# main.net
KiCad netlist of a schematic drawn in EAGLE
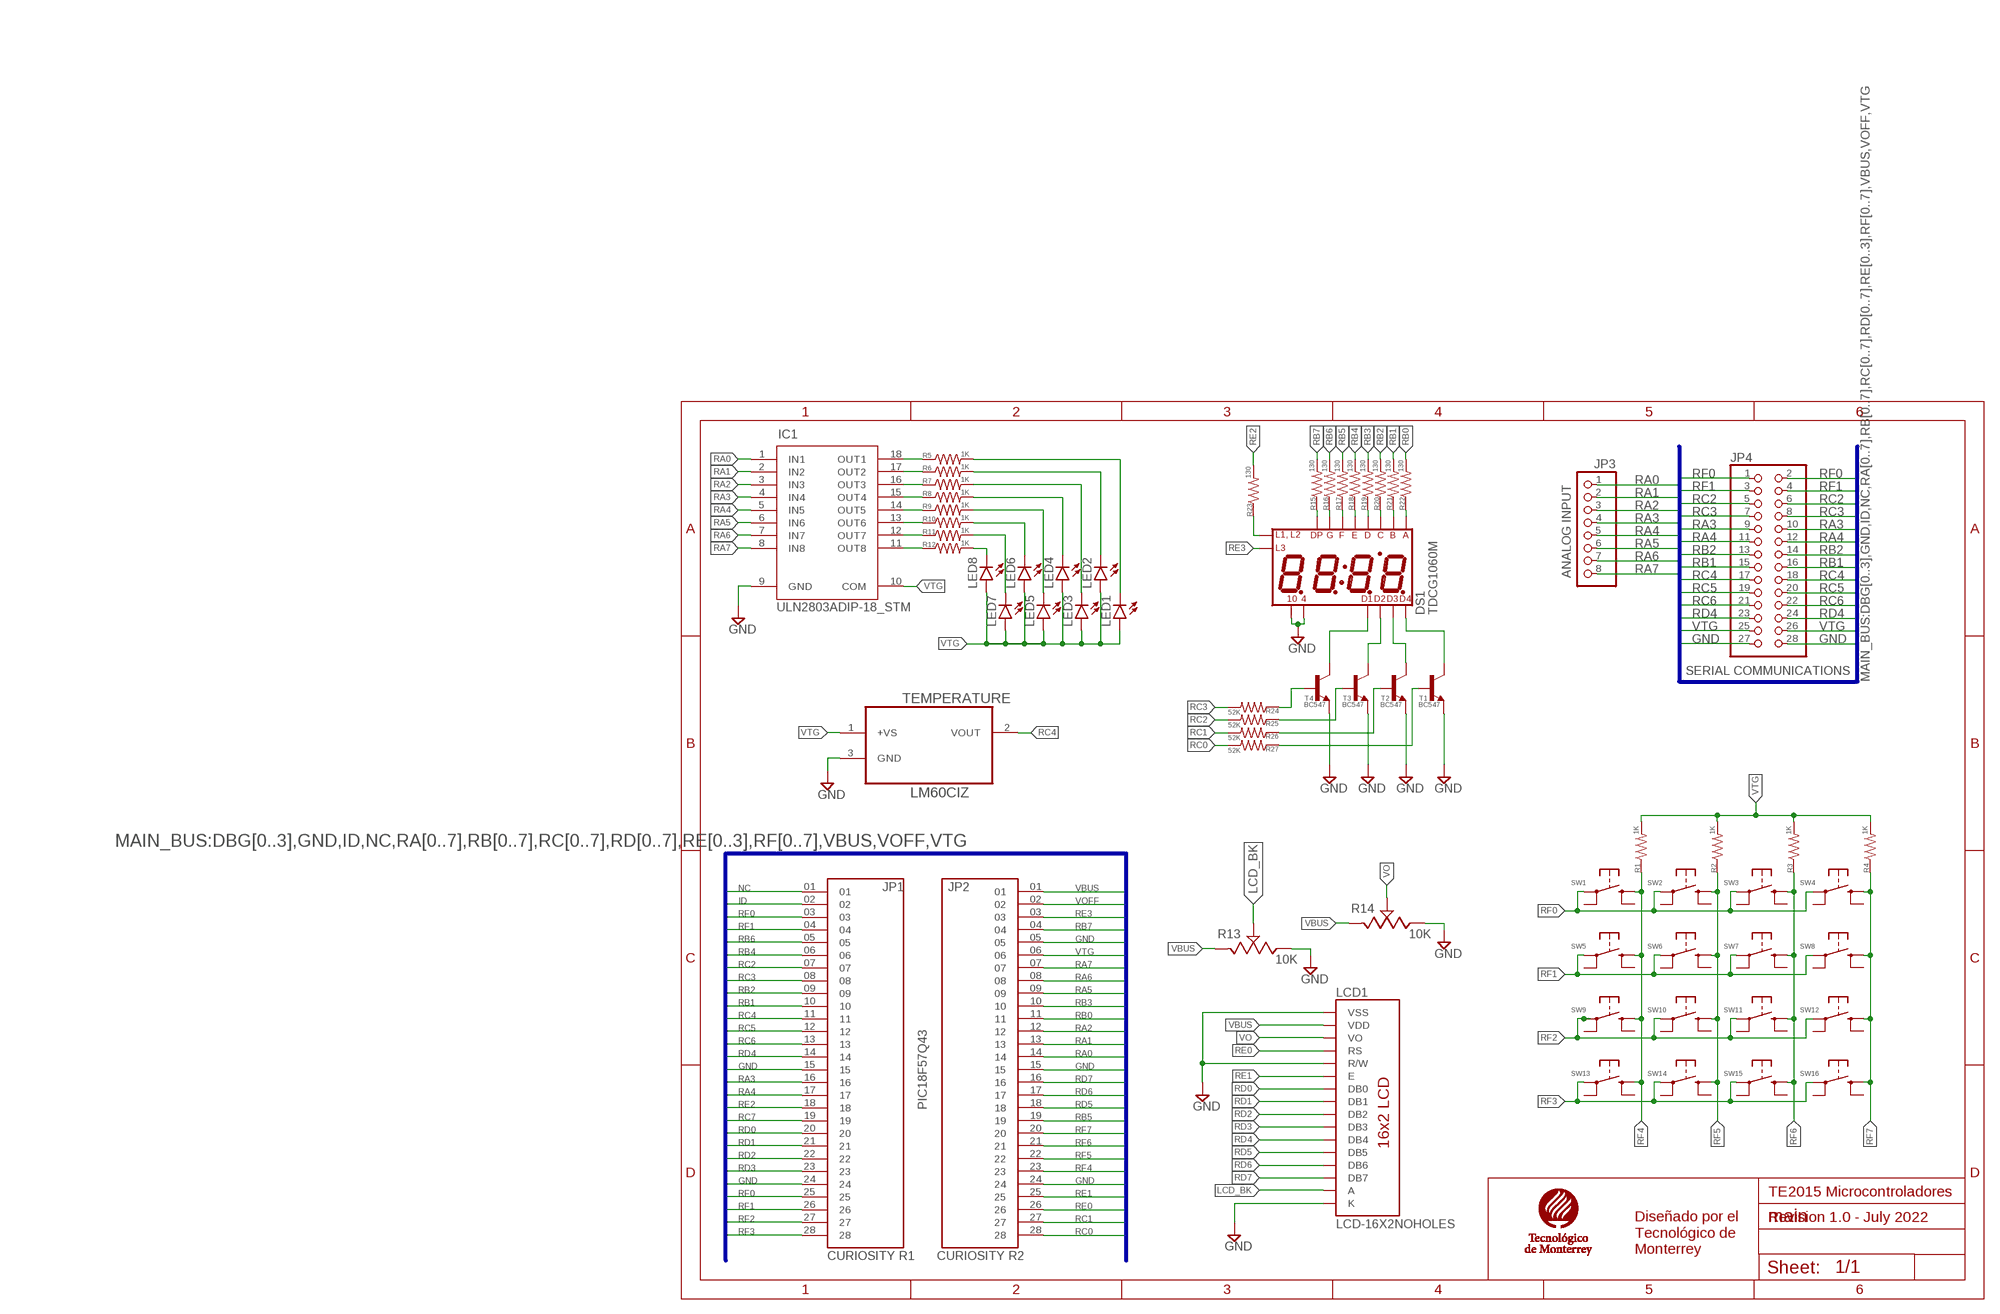
[diagram p0: schematic, sheet 1]

(export (version "E")
  (design (tool "Eeschema 10.0.6"))
  (components
    (comp (ref "DS1")
      (value "TDCG1060M")
      (footprint "eagle-import:DISPLAY_TDCG1060M")
      (fields (field (name "DIGI-KEY_PART_NUMBER") "TDCG1060M-ND") (field (name "MF") "Vishay"))
      (libsource (lib "eagle-import") (part "TDCG1060M"))
    )
    (comp (ref "IC1")
      (value "ULN2803ADIP-18_STM")
      (footprint "eagle-import:DIP-18_STM")
      (fields
        (field (name "MANUFACTURER_PART_NUMBER") "ULN2803A")
        (field (name "COPYRIGHT") "Copyright (C) 2022 Ultra Librarian. All rights reserved.")
      )
      (libsource (lib "eagle-import") (part "ULN2803ADIP-18_STM"))
    )
    (comp (ref "JP1")
      (value "CURIOSITY R1")
      (footprint "eagle-import:SAMTEC_SS-128-T-2")
      (fields
        (field (name "DIGI-KEY_PART_NUMBER") "SAM1117-28-ND")
        (field (name "MF") "Samtec")
        (field (name "MP") "SS-128-T-2")
      )
      (libsource (lib "eagle-import") (part "SS-128-T-2"))
    )
    (comp (ref "JP2")
      (value "CURIOSITY R2")
      (footprint "eagle-import:SAMTEC_SS-128-T-2")
      (fields
        (field (name "DIGI-KEY_PART_NUMBER") "SAM1117-28-ND")
        (field (name "MF") "Samtec")
        (field (name "MP") "SS-128-T-2")
      )
      (libsource (lib "eagle-import") (part "SS-128-T-2"))
    )
    (comp (ref "JP3")
      (value "ANALOG INPUT")
      (footprint "eagle-import:1X08-BIG")
      (libsource (lib "eagle-import") (part "PINHD-1X8BIG"))
    )
    (comp (ref "JP4")
      (value "SERIAL COMMUNICATIONS")
      (footprint "eagle-import:2X14-BIG")
      (libsource (lib "eagle-import") (part "PINHD-2X14-CB"))
    )
    (comp (ref "LCD1")
      (value "LCD-16X2NOHOLES")
      (footprint "eagle-import:LCD-16X2_NOHOLESNOSILK")
      (libsource (lib "eagle-import") (part "LCD-16X2NOHOLES"))
    )
    (comp (ref "LED1")
      (value "LED3MM")
      (footprint "eagle-import:LED3MM")
      (libsource (lib "eagle-import") (part "LED3MM"))
    )
    (comp (ref "LED2")
      (value "LED3MM")
      (footprint "eagle-import:LED3MM")
      (libsource (lib "eagle-import") (part "LED3MM"))
    )
    (comp (ref "LED3")
      (value "LED3MM")
      (footprint "eagle-import:LED3MM")
      (libsource (lib "eagle-import") (part "LED3MM"))
    )
    (comp (ref "LED4")
      (value "LED3MM")
      (footprint "eagle-import:LED3MM")
      (libsource (lib "eagle-import") (part "LED3MM"))
    )
    (comp (ref "LED5")
      (value "LED3MM")
      (footprint "eagle-import:LED3MM")
      (libsource (lib "eagle-import") (part "LED3MM"))
    )
    (comp (ref "LED6")
      (value "LED3MM")
      (footprint "eagle-import:LED3MM")
      (libsource (lib "eagle-import") (part "LED3MM"))
    )
    (comp (ref "LED7")
      (value "LED3MM")
      (footprint "eagle-import:LED3MM")
      (libsource (lib "eagle-import") (part "LED3MM"))
    )
    (comp (ref "LED8")
      (value "LED3MM")
      (footprint "eagle-import:LED3MM")
      (libsource (lib "eagle-import") (part "LED3MM"))
    )
    (comp (ref "R1")
      (value "1K")
      (footprint "eagle-import:0207_10")
      (libsource (lib "eagle-import") (part "R-US"))
    )
    (comp (ref "R2")
      (value "1K")
      (footprint "eagle-import:0207_10")
      (libsource (lib "eagle-import") (part "R-US"))
    )
    (comp (ref "R3")
      (value "1K")
      (footprint "eagle-import:0207_10")
      (libsource (lib "eagle-import") (part "R-US"))
    )
    (comp (ref "R4")
      (value "1K")
      (footprint "eagle-import:0207_10")
      (libsource (lib "eagle-import") (part "R-US"))
    )
    (comp (ref "R5")
      (value "1K")
      (footprint "eagle-import:0207_10")
      (libsource (lib "eagle-import") (part "R-US"))
    )
    (comp (ref "R6")
      (value "1K")
      (footprint "eagle-import:0207_10")
      (libsource (lib "eagle-import") (part "R-US"))
    )
    (comp (ref "R7")
      (value "1K")
      (footprint "eagle-import:0207_10")
      (libsource (lib "eagle-import") (part "R-US"))
    )
    (comp (ref "R8")
      (value "1K")
      (footprint "eagle-import:0207_10")
      (libsource (lib "eagle-import") (part "R-US"))
    )
    (comp (ref "R9")
      (value "1K")
      (footprint "eagle-import:0207_10")
      (libsource (lib "eagle-import") (part "R-US"))
    )
    (comp (ref "R10")
      (value "1K")
      (footprint "eagle-import:0207_10")
      (libsource (lib "eagle-import") (part "R-US"))
    )
    (comp (ref "R11")
      (value "1K")
      (footprint "eagle-import:0207_10")
      (libsource (lib "eagle-import") (part "R-US"))
    )
    (comp (ref "R12")
      (value "1K")
      (footprint "eagle-import:0207_10")
      (libsource (lib "eagle-import") (part "R-US"))
    )
    (comp (ref "R13")
      (value "10K")
      (footprint "eagle-import:3362P-1-103LF")
      (fields
        (field (name "MANUFACTURER") "Bourns Inc.")
        (field (name "MPN") "3362P-1-103LF")
        (field (name "CREATED_PN") "PCBLayout.com")
      )
      (libsource (lib "eagle-import") (part "3362P-1-103LF"))
    )
    (comp (ref "R14")
      (value "10K")
      (footprint "eagle-import:3362P-1-103LF")
      (fields
        (field (name "MANUFACTURER") "Bourns Inc.")
        (field (name "MPN") "3362P-1-103LF")
        (field (name "CREATED_PN") "PCBLayout.com")
      )
      (libsource (lib "eagle-import") (part "3362P-1-103LF"))
    )
    (comp (ref "R15")
      (value "130")
      (footprint "eagle-import:0207_10")
      (libsource (lib "eagle-import") (part "R-US"))
    )
    (comp (ref "R16")
      (value "130")
      (footprint "eagle-import:0207_10")
      (libsource (lib "eagle-import") (part "R-US"))
    )
    (comp (ref "R17")
      (value "130")
      (footprint "eagle-import:0207_10")
      (libsource (lib "eagle-import") (part "R-US"))
    )
    (comp (ref "R18")
      (value "130")
      (footprint "eagle-import:0207_10")
      (libsource (lib "eagle-import") (part "R-US"))
    )
    (comp (ref "R19")
      (value "130")
      (footprint "eagle-import:0207_10")
      (libsource (lib "eagle-import") (part "R-US"))
    )
    (comp (ref "R20")
      (value "130")
      (footprint "eagle-import:0207_10")
      (libsource (lib "eagle-import") (part "R-US"))
    )
    (comp (ref "R21")
      (value "130")
      (footprint "eagle-import:0207_10")
      (libsource (lib "eagle-import") (part "R-US"))
    )
    (comp (ref "R22")
      (value "130")
      (footprint "eagle-import:0207_10")
      (libsource (lib "eagle-import") (part "R-US"))
    )
    (comp (ref "R23")
      (value "130")
      (footprint "eagle-import:0207_10")
      (libsource (lib "eagle-import") (part "R-US"))
    )
    (comp (ref "R24")
      (value "52K")
      (footprint "eagle-import:0207_10")
      (libsource (lib "eagle-import") (part "R-US"))
    )
    (comp (ref "R25")
      (value "52K")
      (footprint "eagle-import:0207_10")
      (libsource (lib "eagle-import") (part "R-US"))
    )
    (comp (ref "R26")
      (value "52K")
      (footprint "eagle-import:0207_10")
      (libsource (lib "eagle-import") (part "R-US"))
    )
    (comp (ref "R27")
      (value "52K")
      (footprint "eagle-import:0207_10")
      (libsource (lib "eagle-import") (part "R-US"))
    )
    (comp (ref "SW1")
      (value "1825910-2")
      (footprint "eagle-import:TE_1825910-2")
      (fields (field (name "MF") "TE Connectivity"))
      (libsource (lib "eagle-import") (part "1825910-2"))
    )
    (comp (ref "SW2")
      (value "1825910-2")
      (footprint "eagle-import:TE_1825910-2")
      (fields (field (name "MF") "TE Connectivity"))
      (libsource (lib "eagle-import") (part "1825910-2"))
    )
    (comp (ref "SW3")
      (value "1825910-2")
      (footprint "eagle-import:TE_1825910-2")
      (fields (field (name "MF") "TE Connectivity"))
      (libsource (lib "eagle-import") (part "1825910-2"))
    )
    (comp (ref "SW4")
      (value "1825910-2")
      (footprint "eagle-import:TE_1825910-2")
      (fields (field (name "MF") "TE Connectivity"))
      (libsource (lib "eagle-import") (part "1825910-2"))
    )
    (comp (ref "SW5")
      (value "1825910-2")
      (footprint "eagle-import:TE_1825910-2")
      (fields (field (name "MF") "TE Connectivity"))
      (libsource (lib "eagle-import") (part "1825910-2"))
    )
    (comp (ref "SW6")
      (value "1825910-2")
      (footprint "eagle-import:TE_1825910-2")
      (fields (field (name "MF") "TE Connectivity"))
      (libsource (lib "eagle-import") (part "1825910-2"))
    )
    (comp (ref "SW7")
      (value "1825910-2")
      (footprint "eagle-import:TE_1825910-2")
      (fields (field (name "MF") "TE Connectivity"))
      (libsource (lib "eagle-import") (part "1825910-2"))
    )
    (comp (ref "SW8")
      (value "1825910-2")
      (footprint "eagle-import:TE_1825910-2")
      (fields (field (name "MF") "TE Connectivity"))
      (libsource (lib "eagle-import") (part "1825910-2"))
    )
    (comp (ref "SW9")
      (value "1825910-2")
      (footprint "eagle-import:TE_1825910-2")
      (fields (field (name "MF") "TE Connectivity"))
      (libsource (lib "eagle-import") (part "1825910-2"))
    )
    (comp (ref "SW10")
      (value "1825910-2")
      (footprint "eagle-import:TE_1825910-2")
      (fields (field (name "MF") "TE Connectivity"))
      (libsource (lib "eagle-import") (part "1825910-2"))
    )
    (comp (ref "SW11")
      (value "1825910-2")
      (footprint "eagle-import:TE_1825910-2")
      (fields (field (name "MF") "TE Connectivity"))
      (libsource (lib "eagle-import") (part "1825910-2"))
    )
    (comp (ref "SW12")
      (value "1825910-2")
      (footprint "eagle-import:TE_1825910-2")
      (fields (field (name "MF") "TE Connectivity"))
      (libsource (lib "eagle-import") (part "1825910-2"))
    )
    (comp (ref "SW13")
      (value "1825910-2")
      (footprint "eagle-import:TE_1825910-2")
      (fields (field (name "MF") "TE Connectivity"))
      (libsource (lib "eagle-import") (part "1825910-2"))
    )
    (comp (ref "SW14")
      (value "1825910-2")
      (footprint "eagle-import:TE_1825910-2")
      (fields (field (name "MF") "TE Connectivity"))
      (libsource (lib "eagle-import") (part "1825910-2"))
    )
    (comp (ref "SW15")
      (value "1825910-2")
      (footprint "eagle-import:TE_1825910-2")
      (fields (field (name "MF") "TE Connectivity"))
      (libsource (lib "eagle-import") (part "1825910-2"))
    )
    (comp (ref "SW16")
      (value "1825910-2")
      (footprint "eagle-import:TE_1825910-2")
      (fields (field (name "MF") "TE Connectivity"))
      (libsource (lib "eagle-import") (part "1825910-2"))
    )
    (comp (ref "T1")
      (value "BC547")
      (footprint "eagle-import:TO92")
      (libsource (lib "eagle-import") (part "BC547"))
    )
    (comp (ref "T2")
      (value "BC547")
      (footprint "eagle-import:TO92")
      (libsource (lib "eagle-import") (part "BC547"))
    )
    (comp (ref "T3")
      (value "BC547")
      (footprint "eagle-import:TO92")
      (libsource (lib "eagle-import") (part "BC547"))
    )
    (comp (ref "T4")
      (value "BC547")
      (footprint "eagle-import:TO92")
      (libsource (lib "eagle-import") (part "BC547"))
    )
    (comp (ref "TEC1")
      (value "TEC_LOGO")
      (footprint "eagle-import:TEC_LOGO")
      (libsource (lib "eagle-import") (part "TEC_LOGO"))
    )
    (comp (ref "TEMPERATURE")
      (value "LM60CIZ")
      (footprint "eagle-import:TO92_")
      (libsource (lib "eagle-import") (part "LM60CIZ"))
    )
  )
  (nets
    (net (code "1") (name "/ID") (class "Default")
      (node (ref "JP1") (pin "02") (pinfunction "02_02") (pintype "passive"))
    )
    (net (code "2") (name "/NC") (class "Default")
      (node (ref "JP1") (pin "01") (pinfunction "01_01") (pintype "passive"))
    )
    (net (code "3") (name "/RC5") (class "Default")
      (node (ref "JP1") (pin "12") (pinfunction "12_12") (pintype "passive"))
      (node (ref "JP4") (pin "19") (pinfunction "19_19") (pintype "passive"))
      (node (ref "JP4") (pin "20") (pinfunction "20_20") (pintype "passive"))
    )
    (net (code "4") (name "/RC6") (class "Default")
      (node (ref "JP1") (pin "13") (pinfunction "13_13") (pintype "passive"))
      (node (ref "JP4") (pin "21") (pinfunction "21_21") (pintype "passive"))
      (node (ref "JP4") (pin "22") (pinfunction "22_22") (pintype "passive"))
    )
    (net (code "5") (name "/RC7") (class "Default")
      (node (ref "JP1") (pin "19") (pinfunction "19_19") (pintype "passive"))
    )
    (net (code "6") (name "/VOFF") (class "Default")
      (node (ref "JP2") (pin "02") (pinfunction "02_02") (pintype "passive"))
    )
    (net (code "8") (name "GND") (class "Default")
      (node (ref "DS1") (pin "10") (pinfunction "10_10") (pintype "passive"))
      (node (ref "DS1") (pin "4") (pinfunction "4_4") (pintype "passive"))
      (node (ref "IC1") (pin "9") (pinfunction "GND_9") (pintype "power_in"))
      (node (ref "JP1") (pin "15") (pinfunction "15_15") (pintype "passive"))
      (node (ref "JP1") (pin "24") (pinfunction "24_24") (pintype "passive"))
      (node (ref "JP2") (pin "05") (pinfunction "05_05") (pintype "passive"))
      (node (ref "JP2") (pin "15") (pinfunction "15_15") (pintype "passive"))
      (node (ref "JP2") (pin "24") (pinfunction "24_24") (pintype "passive"))
      (node (ref "JP4") (pin "27") (pinfunction "27_27") (pintype "passive"))
      (node (ref "JP4") (pin "28") (pinfunction "28_28") (pintype "passive"))
      (node (ref "LCD1") (pin "1") (pinfunction "VSS_1") (pintype "power_in"))
      (node (ref "LCD1") (pin "16") (pinfunction "K_16") (pintype "power_in"))
      (node (ref "LCD1") (pin "5") (pinfunction "R/W_5") (pintype "input"))
      (node (ref "R13") (pin "3") (pinfunction "3_3") (pintype "passive"))
      (node (ref "R14") (pin "3") (pinfunction "3_3") (pintype "passive"))
      (node (ref "T1") (pin "1") (pinfunction "E_1") (pintype "passive"))
      (node (ref "T2") (pin "1") (pinfunction "E_1") (pintype "passive"))
      (node (ref "T3") (pin "1") (pinfunction "E_1") (pintype "passive"))
      (node (ref "T4") (pin "1") (pinfunction "E_1") (pintype "passive"))
      (node (ref "TEMPERATURE") (pin "3") (pinfunction "GND_3") (pintype "passive"))
    )
    (net (code "9") (name "LCD_BK") (class "Default")
      (node (ref "LCD1") (pin "15") (pinfunction "A_15") (pintype "power_in"))
      (node (ref "R13") (pin "2") (pinfunction "2_2") (pintype "passive"))
    )
    (net (code "10") (name "Net-(DS1-A)") (class "Default")
      (node (ref "DS1") (pin "14") (pinfunction "A_14") (pintype "passive"))
      (node (ref "R22") (pin "1") (pinfunction "1_1") (pintype "passive"))
    )
    (net (code "11") (name "Net-(DS1-B)") (class "Default")
      (node (ref "DS1") (pin "16") (pinfunction "B_16") (pintype "passive"))
      (node (ref "R21") (pin "1") (pinfunction "1_1") (pintype "passive"))
    )
    (net (code "12") (name "Net-(DS1-C)") (class "Default")
      (node (ref "DS1") (pin "13") (pinfunction "C_13") (pintype "passive"))
      (node (ref "R20") (pin "1") (pinfunction "1_1") (pintype "passive"))
    )
    (net (code "13") (name "Net-(DS1-D)") (class "Default")
      (node (ref "DS1") (pin "3") (pinfunction "D_3") (pintype "passive"))
      (node (ref "R19") (pin "1") (pinfunction "1_1") (pintype "passive"))
    )
    (net (code "14") (name "Net-(DS1-DIG1)") (class "Default")
      (node (ref "DS1") (pin "1") (pinfunction "DIG1_1") (pintype "passive"))
      (node (ref "T4") (pin "3") (pinfunction "C_3") (pintype "passive"))
    )
    (net (code "15") (name "Net-(DS1-DIG2)") (class "Default")
      (node (ref "DS1") (pin "2") (pinfunction "DIG2_2") (pintype "passive"))
      (node (ref "T3") (pin "3") (pinfunction "C_3") (pintype "passive"))
    )
    (net (code "16") (name "Net-(DS1-DIG3)") (class "Default")
      (node (ref "DS1") (pin "6") (pinfunction "DIG3_6") (pintype "passive"))
      (node (ref "T2") (pin "3") (pinfunction "C_3") (pintype "passive"))
    )
    (net (code "17") (name "Net-(DS1-DIG4)") (class "Default")
      (node (ref "DS1") (pin "8") (pinfunction "DIG4_8") (pintype "passive"))
      (node (ref "T1") (pin "3") (pinfunction "C_3") (pintype "passive"))
    )
    (net (code "18") (name "Net-(DS1-DP)") (class "Default")
      (node (ref "DS1") (pin "7") (pinfunction "DP_7") (pintype "passive"))
      (node (ref "R15") (pin "1") (pinfunction "1_1") (pintype "passive"))
    )
    (net (code "19") (name "Net-(DS1-E)") (class "Default")
      (node (ref "DS1") (pin "5") (pinfunction "E_5") (pintype "passive"))
      (node (ref "R18") (pin "1") (pinfunction "1_1") (pintype "passive"))
    )
    (net (code "20") (name "Net-(DS1-F)") (class "Default")
      (node (ref "DS1") (pin "11") (pinfunction "F_11") (pintype "passive"))
      (node (ref "R17") (pin "1") (pinfunction "1_1") (pintype "passive"))
    )
    (net (code "21") (name "Net-(DS1-G)") (class "Default")
      (node (ref "DS1") (pin "15") (pinfunction "G_15") (pintype "passive"))
      (node (ref "R16") (pin "1") (pinfunction "1_1") (pintype "passive"))
    )
    (net (code "22") (name "Net-(DS1-L1_L2)") (class "Default")
      (node (ref "DS1") (pin "12") (pinfunction "L1_L2_12") (pintype "passive"))
      (node (ref "R23") (pin "1") (pinfunction "1_1") (pintype "passive"))
    )
    (net (code "23") (name "Net-(IC1-OUT1)") (class "Default")
      (node (ref "IC1") (pin "18") (pinfunction "OUT1_18") (pintype "passive"))
      (node (ref "R5") (pin "1") (pinfunction "1_1") (pintype "passive"))
    )
    (net (code "24") (name "Net-(IC1-OUT2)") (class "Default")
      (node (ref "IC1") (pin "17") (pinfunction "OUT2_17") (pintype "passive"))
      (node (ref "R6") (pin "1") (pinfunction "1_1") (pintype "passive"))
    )
    (net (code "25") (name "Net-(IC1-OUT3)") (class "Default")
      (node (ref "IC1") (pin "16") (pinfunction "OUT3_16") (pintype "passive"))
      (node (ref "R7") (pin "1") (pinfunction "1_1") (pintype "passive"))
    )
    (net (code "26") (name "Net-(IC1-OUT4)") (class "Default")
      (node (ref "IC1") (pin "15") (pinfunction "OUT4_15") (pintype "passive"))
      (node (ref "R8") (pin "1") (pinfunction "1_1") (pintype "passive"))
    )
    (net (code "27") (name "Net-(IC1-OUT5)") (class "Default")
      (node (ref "IC1") (pin "14") (pinfunction "OUT5_14") (pintype "passive"))
      (node (ref "R9") (pin "1") (pinfunction "1_1") (pintype "passive"))
    )
    (net (code "28") (name "Net-(IC1-OUT6)") (class "Default")
      (node (ref "IC1") (pin "13") (pinfunction "OUT6_13") (pintype "passive"))
      (node (ref "R10") (pin "1") (pinfunction "1_1") (pintype "passive"))
    )
    (net (code "29") (name "Net-(IC1-OUT7)") (class "Default")
      (node (ref "IC1") (pin "12") (pinfunction "OUT7_12") (pintype "passive"))
      (node (ref "R11") (pin "1") (pinfunction "1_1") (pintype "passive"))
    )
    (net (code "30") (name "Net-(IC1-OUT8)") (class "Default")
      (node (ref "IC1") (pin "11") (pinfunction "OUT8_11") (pintype "passive"))
      (node (ref "R12") (pin "1") (pinfunction "1_1") (pintype "passive"))
    )
    (net (code "31") (name "Net-(LED1-C)") (class "Default")
      (node (ref "LED1") (pin "K") (pinfunction "C_K") (pintype "passive"))
      (node (ref "R5") (pin "2") (pinfunction "2_2") (pintype "passive"))
    )
    (net (code "32") (name "Net-(LED2-C)") (class "Default")
      (node (ref "LED2") (pin "K") (pinfunction "C_K") (pintype "passive"))
      (node (ref "R6") (pin "2") (pinfunction "2_2") (pintype "passive"))
    )
    (net (code "33") (name "Net-(LED3-C)") (class "Default")
      (node (ref "LED3") (pin "K") (pinfunction "C_K") (pintype "passive"))
      (node (ref "R7") (pin "2") (pinfunction "2_2") (pintype "passive"))
    )
    (net (code "34") (name "Net-(LED4-C)") (class "Default")
      (node (ref "LED4") (pin "K") (pinfunction "C_K") (pintype "passive"))
      (node (ref "R8") (pin "2") (pinfunction "2_2") (pintype "passive"))
    )
    (net (code "35") (name "Net-(LED5-C)") (class "Default")
      (node (ref "LED5") (pin "K") (pinfunction "C_K") (pintype "passive"))
      (node (ref "R9") (pin "2") (pinfunction "2_2") (pintype "passive"))
    )
    (net (code "36") (name "Net-(LED6-C)") (class "Default")
      (node (ref "LED6") (pin "K") (pinfunction "C_K") (pintype "passive"))
      (node (ref "R10") (pin "2") (pinfunction "2_2") (pintype "passive"))
    )
    (net (code "37") (name "Net-(LED7-C)") (class "Default")
      (node (ref "LED7") (pin "K") (pinfunction "C_K") (pintype "passive"))
      (node (ref "R11") (pin "2") (pinfunction "2_2") (pintype "passive"))
    )
    (net (code "38") (name "Net-(LED8-C)") (class "Default")
      (node (ref "LED8") (pin "K") (pinfunction "C_K") (pintype "passive"))
      (node (ref "R12") (pin "2") (pinfunction "2_2") (pintype "passive"))
    )
    (net (code "39") (name "Net-(T1-B)") (class "Default")
      (node (ref "R27") (pin "1") (pinfunction "1_1") (pintype "passive"))
      (node (ref "T1") (pin "2") (pinfunction "B_2") (pintype "passive"))
    )
    (net (code "40") (name "Net-(T2-B)") (class "Default")
      (node (ref "R26") (pin "1") (pinfunction "1_1") (pintype "passive"))
      (node (ref "T2") (pin "2") (pinfunction "B_2") (pintype "passive"))
    )
    (net (code "41") (name "Net-(T3-B)") (class "Default")
      (node (ref "R25") (pin "1") (pinfunction "1_1") (pintype "passive"))
      (node (ref "T3") (pin "2") (pinfunction "B_2") (pintype "passive"))
    )
    (net (code "42") (name "Net-(T4-B)") (class "Default")
      (node (ref "R24") (pin "1") (pinfunction "1_1") (pintype "passive"))
      (node (ref "T4") (pin "2") (pinfunction "B_2") (pintype "passive"))
    )
    (net (code "43") (name "RA0") (class "Default")
      (node (ref "IC1") (pin "1") (pinfunction "IN1_1") (pintype "input"))
      (node (ref "JP2") (pin "14") (pinfunction "14_14") (pintype "passive"))
      (node (ref "JP3") (pin "1") (pinfunction "1_1") (pintype "passive"))
    )
    (net (code "44") (name "RA1") (class "Default")
      (node (ref "IC1") (pin "2") (pinfunction "IN2_2") (pintype "input"))
      (node (ref "JP2") (pin "13") (pinfunction "13_13") (pintype "passive"))
      (node (ref "JP3") (pin "2") (pinfunction "2_2") (pintype "passive"))
    )
    (net (code "45") (name "RA2") (class "Default")
      (node (ref "IC1") (pin "3") (pinfunction "IN3_3") (pintype "input"))
      (node (ref "JP2") (pin "12") (pinfunction "12_12") (pintype "passive"))
      (node (ref "JP3") (pin "3") (pinfunction "3_3") (pintype "passive"))
    )
    (net (code "46") (name "RA3") (class "Default")
      (node (ref "IC1") (pin "4") (pinfunction "IN4_4") (pintype "input"))
      (node (ref "JP1") (pin "16") (pinfunction "16_16") (pintype "passive"))
      (node (ref "JP3") (pin "4") (pinfunction "4_4") (pintype "passive"))
      (node (ref "JP4") (pin "10") (pinfunction "10_10") (pintype "passive"))
      (node (ref "JP4") (pin "9") (pinfunction "9_9") (pintype "passive"))
    )
    (net (code "47") (name "RA4") (class "Default")
      (node (ref "IC1") (pin "5") (pinfunction "IN5_5") (pintype "input"))
      (node (ref "JP1") (pin "17") (pinfunction "17_17") (pintype "passive"))
      (node (ref "JP3") (pin "5") (pinfunction "5_5") (pintype "passive"))
      (node (ref "JP4") (pin "11") (pinfunction "11_11") (pintype "passive"))
      (node (ref "JP4") (pin "12") (pinfunction "12_12") (pintype "passive"))
    )
    (net (code "48") (name "RA5") (class "Default")
      (node (ref "IC1") (pin "6") (pinfunction "IN6_6") (pintype "input"))
      (node (ref "JP2") (pin "09") (pinfunction "09_09") (pintype "passive"))
      (node (ref "JP3") (pin "6") (pinfunction "6_6") (pintype "passive"))
    )
    (net (code "49") (name "RA6") (class "Default")
      (node (ref "IC1") (pin "7") (pinfunction "IN7_7") (pintype "input"))
      (node (ref "JP2") (pin "08") (pinfunction "08_08") (pintype "passive"))
      (node (ref "JP3") (pin "7") (pinfunction "7_7") (pintype "passive"))
    )
    (net (code "50") (name "RA7") (class "Default")
      (node (ref "IC1") (pin "8") (pinfunction "IN8_8") (pintype "input"))
      (node (ref "JP2") (pin "07") (pinfunction "07_07") (pintype "passive"))
      (node (ref "JP3") (pin "8") (pinfunction "8_8") (pintype "passive"))
    )
    (net (code "51") (name "RB0") (class "Default")
      (node (ref "JP2") (pin "11") (pinfunction "11_11") (pintype "passive"))
      (node (ref "R22") (pin "2") (pinfunction "2_2") (pintype "passive"))
    )
    (net (code "52") (name "RB1") (class "Default")
      (node (ref "JP1") (pin "10") (pinfunction "10_10") (pintype "passive"))
      (node (ref "JP4") (pin "15") (pinfunction "15_15") (pintype "passive"))
      (node (ref "JP4") (pin "16") (pinfunction "16_16") (pintype "passive"))
      (node (ref "R21") (pin "2") (pinfunction "2_2") (pintype "passive"))
    )
    (net (code "53") (name "RB2") (class "Default")
      (node (ref "JP1") (pin "09") (pinfunction "09_09") (pintype "passive"))
      (node (ref "JP4") (pin "13") (pinfunction "13_13") (pintype "passive"))
      (node (ref "JP4") (pin "14") (pinfunction "14_14") (pintype "passive"))
      (node (ref "R20") (pin "2") (pinfunction "2_2") (pintype "passive"))
    )
    (net (code "54") (name "RB3") (class "Default")
      (node (ref "JP2") (pin "10") (pinfunction "10_10") (pintype "passive"))
      (node (ref "R19") (pin "2") (pinfunction "2_2") (pintype "passive"))
    )
    (net (code "55") (name "RB4") (class "Default")
      (node (ref "JP1") (pin "06") (pinfunction "06_06") (pintype "passive"))
      (node (ref "R18") (pin "2") (pinfunction "2_2") (pintype "passive"))
    )
    (net (code "56") (name "RB5") (class "Default")
      (node (ref "JP2") (pin "19") (pinfunction "19_19") (pintype "passive"))
      (node (ref "R17") (pin "2") (pinfunction "2_2") (pintype "passive"))
    )
    (net (code "57") (name "RB6") (class "Default")
      (node (ref "JP1") (pin "05") (pinfunction "05_05") (pintype "passive"))
      (node (ref "R16") (pin "2") (pinfunction "2_2") (pintype "passive"))
    )
    (net (code "58") (name "RB7") (class "Default")
      (node (ref "JP2") (pin "04") (pinfunction "04_04") (pintype "passive"))
      (node (ref "R15") (pin "2") (pinfunction "2_2") (pintype "passive"))
    )
    (net (code "59") (name "RC0") (class "Default")
      (node (ref "JP2") (pin "28") (pinfunction "28_28") (pintype "passive"))
      (node (ref "R27") (pin "2") (pinfunction "2_2") (pintype "passive"))
    )
    (net (code "60") (name "RC1") (class "Default")
      (node (ref "JP2") (pin "27") (pinfunction "27_27") (pintype "passive"))
      (node (ref "R26") (pin "2") (pinfunction "2_2") (pintype "passive"))
    )
    (net (code "61") (name "RC2") (class "Default")
      (node (ref "JP1") (pin "07") (pinfunction "07_07") (pintype "passive"))
      (node (ref "JP4") (pin "5") (pinfunction "5_5") (pintype "passive"))
      (node (ref "JP4") (pin "6") (pinfunction "6_6") (pintype "passive"))
      (node (ref "R25") (pin "2") (pinfunction "2_2") (pintype "passive"))
    )
    (net (code "62") (name "RC3") (class "Default")
      (node (ref "JP1") (pin "08") (pinfunction "08_08") (pintype "passive"))
      (node (ref "JP4") (pin "7") (pinfunction "7_7") (pintype "passive"))
      (node (ref "JP4") (pin "8") (pinfunction "8_8") (pintype "passive"))
      (node (ref "R24") (pin "2") (pinfunction "2_2") (pintype "passive"))
    )
    (net (code "63") (name "RC4") (class "Default")
      (node (ref "JP1") (pin "11") (pinfunction "11_11") (pintype "passive"))
      (node (ref "JP4") (pin "17") (pinfunction "17_17") (pintype "passive"))
      (node (ref "JP4") (pin "18") (pinfunction "18_18") (pintype "passive"))
      (node (ref "TEMPERATURE") (pin "2") (pinfunction "VOUT_2") (pintype "output"))
    )
    (net (code "64") (name "RD0") (class "Default")
      (node (ref "JP1") (pin "20") (pinfunction "20_20") (pintype "passive"))
      (node (ref "LCD1") (pin "7") (pinfunction "DB0_7") (pintype "bidirectional"))
    )
    (net (code "65") (name "RD1") (class "Default")
      (node (ref "JP1") (pin "21") (pinfunction "21_21") (pintype "passive"))
      (node (ref "LCD1") (pin "8") (pinfunction "DB1_8") (pintype "bidirectional"))
    )
    (net (code "66") (name "RD2") (class "Default")
      (node (ref "JP1") (pin "22") (pinfunction "22_22") (pintype "passive"))
      (node (ref "LCD1") (pin "9") (pinfunction "DB2_9") (pintype "bidirectional"))
    )
    (net (code "67") (name "RD3") (class "Default")
      (node (ref "JP1") (pin "23") (pinfunction "23_23") (pintype "passive"))
      (node (ref "LCD1") (pin "10") (pinfunction "DB3_10") (pintype "bidirectional"))
    )
    (net (code "68") (name "RD4") (class "Default")
      (node (ref "JP1") (pin "14") (pinfunction "14_14") (pintype "passive"))
      (node (ref "JP4") (pin "23") (pinfunction "23_23") (pintype "passive"))
      (node (ref "JP4") (pin "24") (pinfunction "24_24") (pintype "passive"))
      (node (ref "LCD1") (pin "11") (pinfunction "DB4_11") (pintype "bidirectional"))
    )
    (net (code "69") (name "RD5") (class "Default")
      (node (ref "JP2") (pin "18") (pinfunction "18_18") (pintype "passive"))
      (node (ref "LCD1") (pin "12") (pinfunction "DB5_12") (pintype "bidirectional"))
    )
    (net (code "70") (name "RD6") (class "Default")
      (node (ref "JP2") (pin "17") (pinfunction "17_17") (pintype "passive"))
      (node (ref "LCD1") (pin "13") (pinfunction "DB6_13") (pintype "bidirectional"))
    )
    (net (code "71") (name "RD7") (class "Default")
      (node (ref "JP2") (pin "16") (pinfunction "16_16") (pintype "passive"))
      (node (ref "LCD1") (pin "14") (pinfunction "DB7_14") (pintype "bidirectional"))
    )
    (net (code "72") (name "RE0") (class "Default")
      (node (ref "JP2") (pin "26") (pinfunction "26_26") (pintype "passive"))
      (node (ref "LCD1") (pin "4") (pinfunction "RS_4") (pintype "input"))
    )
    (net (code "73") (name "RE1") (class "Default")
      (node (ref "JP2") (pin "25") (pinfunction "25_25") (pintype "passive"))
      (node (ref "LCD1") (pin "6") (pinfunction "E_6") (pintype "input"))
    )
    (net (code "74") (name "RE2") (class "Default")
      (node (ref "JP1") (pin "18") (pinfunction "18_18") (pintype "passive"))
      (node (ref "R23") (pin "2") (pinfunction "2_2") (pintype "passive"))
    )
    (net (code "75") (name "RE3") (class "Default")
      (node (ref "DS1") (pin "9") (pinfunction "L3_9") (pintype "passive"))
      (node (ref "JP2") (pin "03") (pinfunction "03_03") (pintype "passive"))
    )
    (net (code "76") (name "RF0") (class "Default")
      (node (ref "JP1") (pin "03") (pinfunction "03_03") (pintype "passive"))
      (node (ref "JP1") (pin "25") (pinfunction "25_25") (pintype "passive"))
      (node (ref "JP4") (pin "1") (pinfunction "1_1") (pintype "passive"))
      (node (ref "JP4") (pin "2") (pinfunction "2_2") (pintype "passive"))
      (node (ref "SW1") (pin "1") (pinfunction "P_1") (pintype "passive"))
      (node (ref "SW2") (pin "1") (pinfunction "P_1") (pintype "passive"))
      (node (ref "SW3") (pin "1") (pinfunction "P_1") (pintype "passive"))
      (node (ref "SW4") (pin "1") (pinfunction "P_1") (pintype "passive"))
    )
    (net (code "77") (name "RF1") (class "Default")
      (node (ref "JP1") (pin "04") (pinfunction "04_04") (pintype "passive"))
      (node (ref "JP1") (pin "26") (pinfunction "26_26") (pintype "passive"))
      (node (ref "JP4") (pin "3") (pinfunction "3_3") (pintype "passive"))
      (node (ref "JP4") (pin "4") (pinfunction "4_4") (pintype "passive"))
      (node (ref "SW5") (pin "1") (pinfunction "P_1") (pintype "passive"))
      (node (ref "SW6") (pin "1") (pinfunction "P_1") (pintype "passive"))
      (node (ref "SW7") (pin "1") (pinfunction "P_1") (pintype "passive"))
      (node (ref "SW8") (pin "1") (pinfunction "P_1") (pintype "passive"))
    )
    (net (code "78") (name "RF2") (class "Default")
      (node (ref "JP1") (pin "27") (pinfunction "27_27") (pintype "passive"))
      (node (ref "SW10") (pin "1") (pinfunction "P_1") (pintype "passive"))
      (node (ref "SW11") (pin "1") (pinfunction "P_1") (pintype "passive"))
      (node (ref "SW12") (pin "1") (pinfunction "P_1") (pintype "passive"))
      (node (ref "SW9") (pin "1") (pinfunction "P_1") (pintype "passive"))
    )
    (net (code "79") (name "RF3") (class "Default")
      (node (ref "JP1") (pin "28") (pinfunction "28_28") (pintype "passive"))
      (node (ref "SW13") (pin "1") (pinfunction "P_1") (pintype "passive"))
      (node (ref "SW14") (pin "1") (pinfunction "P_1") (pintype "passive"))
      (node (ref "SW15") (pin "1") (pinfunction "P_1") (pintype "passive"))
      (node (ref "SW16") (pin "1") (pinfunction "P_1") (pintype "passive"))
    )
    (net (code "80") (name "RF4") (class "Default")
      (node (ref "JP2") (pin "23") (pinfunction "23_23") (pintype "passive"))
      (node (ref "R1") (pin "1") (pinfunction "1_1") (pintype "passive"))
      (node (ref "SW1") (pin "2") (pinfunction "S_2") (pintype "passive"))
      (node (ref "SW13") (pin "2") (pinfunction "S_2") (pintype "passive"))
      (node (ref "SW5") (pin "2") (pinfunction "S_2") (pintype "passive"))
      (node (ref "SW9") (pin "2") (pinfunction "S_2") (pintype "passive"))
    )
    (net (code "81") (name "RF5") (class "Default")
      (node (ref "JP2") (pin "22") (pinfunction "22_22") (pintype "passive"))
      (node (ref "R2") (pin "1") (pinfunction "1_1") (pintype "passive"))
      (node (ref "SW10") (pin "2") (pinfunction "S_2") (pintype "passive"))
      (node (ref "SW14") (pin "2") (pinfunction "S_2") (pintype "passive"))
      (node (ref "SW2") (pin "2") (pinfunction "S_2") (pintype "passive"))
      (node (ref "SW6") (pin "2") (pinfunction "S_2") (pintype "passive"))
    )
    (net (code "82") (name "RF6") (class "Default")
      (node (ref "JP2") (pin "21") (pinfunction "21_21") (pintype "passive"))
      (node (ref "R3") (pin "1") (pinfunction "1_1") (pintype "passive"))
      (node (ref "SW11") (pin "2") (pinfunction "S_2") (pintype "passive"))
      (node (ref "SW15") (pin "2") (pinfunction "S_2") (pintype "passive"))
      (node (ref "SW3") (pin "2") (pinfunction "S_2") (pintype "passive"))
      (node (ref "SW7") (pin "2") (pinfunction "S_2") (pintype "passive"))
    )
    (net (code "83") (name "RF7") (class "Default")
      (node (ref "JP2") (pin "20") (pinfunction "20_20") (pintype "passive"))
      (node (ref "R4") (pin "1") (pinfunction "1_1") (pintype "passive"))
      (node (ref "SW12") (pin "2") (pinfunction "S_2") (pintype "passive"))
      (node (ref "SW16") (pin "2") (pinfunction "S_2") (pintype "passive"))
      (node (ref "SW4") (pin "2") (pinfunction "S_2") (pintype "passive"))
      (node (ref "SW8") (pin "2") (pinfunction "S_2") (pintype "passive"))
    )
    (net (code "84") (name "VBUS") (class "Default")
      (node (ref "JP2") (pin "01") (pinfunction "01_01") (pintype "passive"))
      (node (ref "LCD1") (pin "2") (pinfunction "VDD_2") (pintype "power_in"))
      (node (ref "R13") (pin "1") (pinfunction "1_1") (pintype "passive"))
      (node (ref "R14") (pin "1") (pinfunction "1_1") (pintype "passive"))
    )
    (net (code "85") (name "VO") (class "Default")
      (node (ref "LCD1") (pin "3") (pinfunction "VO_3") (pintype "bidirectional"))
      (node (ref "R14") (pin "2") (pinfunction "2_2") (pintype "passive"))
    )
    (net (code "86") (name "VTG") (class "Default")
      (node (ref "IC1") (pin "10") (pinfunction "COM_10") (pintype "passive"))
      (node (ref "JP2") (pin "06") (pinfunction "06_06") (pintype "passive"))
      (node (ref "JP4") (pin "25") (pinfunction "25_25") (pintype "passive"))
      (node (ref "JP4") (pin "26") (pinfunction "26_26") (pintype "passive"))
      (node (ref "LED1") (pin "A") (pinfunction "A_A") (pintype "passive"))
      (node (ref "LED2") (pin "A") (pinfunction "A_A") (pintype "passive"))
      (node (ref "LED3") (pin "A") (pinfunction "A_A") (pintype "passive"))
      (node (ref "LED4") (pin "A") (pinfunction "A_A") (pintype "passive"))
      (node (ref "LED5") (pin "A") (pinfunction "A_A") (pintype "passive"))
      (node (ref "LED6") (pin "A") (pinfunction "A_A") (pintype "passive"))
      (node (ref "LED7") (pin "A") (pinfunction "A_A") (pintype "passive"))
      (node (ref "LED8") (pin "A") (pinfunction "A_A") (pintype "passive"))
      (node (ref "R1") (pin "2") (pinfunction "2_2") (pintype "passive"))
      (node (ref "R2") (pin "2") (pinfunction "2_2") (pintype "passive"))
      (node (ref "R3") (pin "2") (pinfunction "2_2") (pintype "passive"))
      (node (ref "R4") (pin "2") (pinfunction "2_2") (pintype "passive"))
      (node (ref "TEMPERATURE") (pin "1") (pinfunction "+VS_1") (pintype "power_in"))
    )
    (net (code "87") (name "unconnected-(SW1-P1-Pad3)") (class "Default")
      (node (ref "SW1") (pin "3") (pinfunction "P1_3") (pintype "passive"))
    )
    (net (code "88") (name "unconnected-(SW1-S1-Pad4)") (class "Default")
      (node (ref "SW1") (pin "4") (pinfunction "S1_4") (pintype "passive"))
    )
    (net (code "89") (name "unconnected-(SW2-P1-Pad3)") (class "Default")
      (node (ref "SW2") (pin "3") (pinfunction "P1_3") (pintype "passive"))
    )
    (net (code "90") (name "unconnected-(SW2-S1-Pad4)") (class "Default")
      (node (ref "SW2") (pin "4") (pinfunction "S1_4") (pintype "passive"))
    )
    (net (code "91") (name "unconnected-(SW3-P1-Pad3)") (class "Default")
      (node (ref "SW3") (pin "3") (pinfunction "P1_3") (pintype "passive"))
    )
    (net (code "92") (name "unconnected-(SW3-S1-Pad4)") (class "Default")
      (node (ref "SW3") (pin "4") (pinfunction "S1_4") (pintype "passive"))
    )
    (net (code "93") (name "unconnected-(SW4-P1-Pad3)") (class "Default")
      (node (ref "SW4") (pin "3") (pinfunction "P1_3") (pintype "passive"))
    )
    (net (code "94") (name "unconnected-(SW4-S1-Pad4)") (class "Default")
      (node (ref "SW4") (pin "4") (pinfunction "S1_4") (pintype "passive"))
    )
    (net (code "95") (name "unconnected-(SW5-P1-Pad3)") (class "Default")
      (node (ref "SW5") (pin "3") (pinfunction "P1_3") (pintype "passive"))
    )
    (net (code "96") (name "unconnected-(SW5-S1-Pad4)") (class "Default")
      (node (ref "SW5") (pin "4") (pinfunction "S1_4") (pintype "passive"))
    )
    (net (code "97") (name "unconnected-(SW6-P1-Pad3)") (class "Default")
      (node (ref "SW6") (pin "3") (pinfunction "P1_3") (pintype "passive"))
    )
    (net (code "98") (name "unconnected-(SW6-S1-Pad4)") (class "Default")
      (node (ref "SW6") (pin "4") (pinfunction "S1_4") (pintype "passive"))
    )
    (net (code "99") (name "unconnected-(SW7-P1-Pad3)") (class "Default")
      (node (ref "SW7") (pin "3") (pinfunction "P1_3") (pintype "passive"))
    )
    (net (code "100") (name "unconnected-(SW7-S1-Pad4)") (class "Default")
      (node (ref "SW7") (pin "4") (pinfunction "S1_4") (pintype "passive"))
    )
    (net (code "101") (name "unconnected-(SW8-P1-Pad3)") (class "Default")
      (node (ref "SW8") (pin "3") (pinfunction "P1_3") (pintype "passive"))
    )
    (net (code "102") (name "unconnected-(SW8-S1-Pad4)") (class "Default")
      (node (ref "SW8") (pin "4") (pinfunction "S1_4") (pintype "passive"))
    )
    (net (code "103") (name "unconnected-(SW9-P1-Pad3)") (class "Default")
      (node (ref "SW9") (pin "3") (pinfunction "P1_3") (pintype "passive"))
    )
    (net (code "104") (name "unconnected-(SW9-S1-Pad4)") (class "Default")
      (node (ref "SW9") (pin "4") (pinfunction "S1_4") (pintype "passive"))
    )
    (net (code "105") (name "unconnected-(SW10-P1-Pad3)") (class "Default")
      (node (ref "SW10") (pin "3") (pinfunction "P1_3") (pintype "passive"))
    )
    (net (code "106") (name "unconnected-(SW10-S1-Pad4)") (class "Default")
      (node (ref "SW10") (pin "4") (pinfunction "S1_4") (pintype "passive"))
    )
    (net (code "107") (name "unconnected-(SW11-P1-Pad3)") (class "Default")
      (node (ref "SW11") (pin "3") (pinfunction "P1_3") (pintype "passive"))
    )
    (net (code "108") (name "unconnected-(SW11-S1-Pad4)") (class "Default")
      (node (ref "SW11") (pin "4") (pinfunction "S1_4") (pintype "passive"))
    )
    (net (code "109") (name "unconnected-(SW12-P1-Pad3)") (class "Default")
      (node (ref "SW12") (pin "3") (pinfunction "P1_3") (pintype "passive"))
    )
    (net (code "110") (name "unconnected-(SW12-S1-Pad4)") (class "Default")
      (node (ref "SW12") (pin "4") (pinfunction "S1_4") (pintype "passive"))
    )
    (net (code "111") (name "unconnected-(SW13-P1-Pad3)") (class "Default")
      (node (ref "SW13") (pin "3") (pinfunction "P1_3") (pintype "passive"))
    )
    (net (code "112") (name "unconnected-(SW13-S1-Pad4)") (class "Default")
      (node (ref "SW13") (pin "4") (pinfunction "S1_4") (pintype "passive"))
    )
    (net (code "113") (name "unconnected-(SW14-P1-Pad3)") (class "Default")
      (node (ref "SW14") (pin "3") (pinfunction "P1_3") (pintype "passive"))
    )
    (net (code "114") (name "unconnected-(SW14-S1-Pad4)") (class "Default")
      (node (ref "SW14") (pin "4") (pinfunction "S1_4") (pintype "passive"))
    )
    (net (code "115") (name "unconnected-(SW15-P1-Pad3)") (class "Default")
      (node (ref "SW15") (pin "3") (pinfunction "P1_3") (pintype "passive"))
    )
    (net (code "116") (name "unconnected-(SW15-S1-Pad4)") (class "Default")
      (node (ref "SW15") (pin "4") (pinfunction "S1_4") (pintype "passive"))
    )
    (net (code "117") (name "unconnected-(SW16-P1-Pad3)") (class "Default")
      (node (ref "SW16") (pin "3") (pinfunction "P1_3") (pintype "passive"))
    )
    (net (code "118") (name "unconnected-(SW16-S1-Pad4)") (class "Default")
      (node (ref "SW16") (pin "4") (pinfunction "S1_4") (pintype "passive"))
    )
  )
)
